# STM32_microcontroller_power.net
KiCad netlist of a schematic drawn in Altium Designer
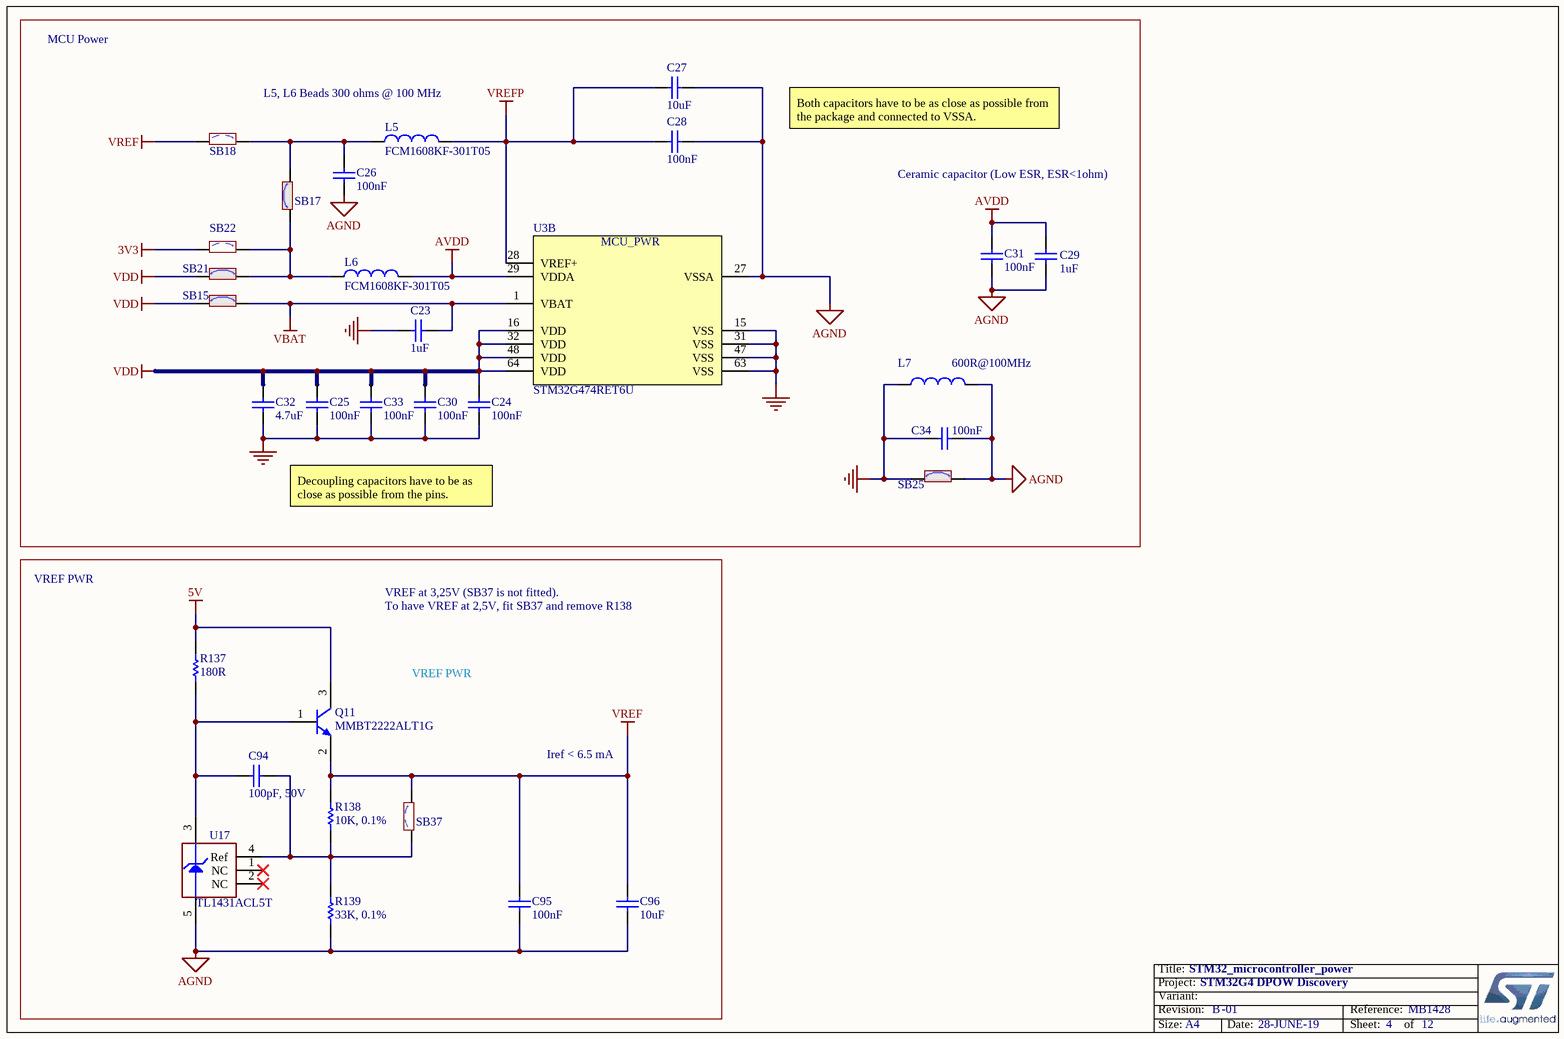
[diagram p0: STM32_microcontroller_power.SchDoc]

(export (version "E")
  (design (tool "Eeschema 10.0.6"))
  (components
    (comp (ref "C23")
      (value "1uF")
      (footprint "C0603")
      (description "Capacitor, MLCC, 1uF, 16V, X5R, 10%, 0603, T=0,8mm")
      (fields
        (field (name "INTERNAL_PART_NUMBER") "MCD-00010")
        (field (name "MANUFACTURER_PART_NUMBER") "CC0603KRX5R7BB105")
        (field (name "PROVIDED_BY") "SUBCO")
      )
      (libsource (lib "MCD_PARTS_database") (part "Capacitor"))
    )
    (comp (ref "C24")
      (value "100nF")
      (footprint "C0402")
      (description "Capacitor, MLCC, 100nF, 16V, X7R, 10%, 0402, T=0,5mm")
      (fields
        (field (name "INTERNAL_PART_NUMBER") "MCD-00102")
        (field (name "MANUFACTURER_PART_NUMBER") "CC0402KRX7R7BB104")
        (field (name "PROVIDED_BY") "SUBCO")
      )
      (libsource (lib "MCD_PARTS_database") (part "Capacitor"))
    )
    (comp (ref "C25")
      (value "100nF")
      (footprint "C0402")
      (description "Capacitor, MLCC, 100nF, 16V, X7R, 10%, 0402, T=0,5mm")
      (fields
        (field (name "INTERNAL_PART_NUMBER") "MCD-00102")
        (field (name "MANUFACTURER_PART_NUMBER") "CC0402KRX7R7BB104")
        (field (name "PROVIDED_BY") "SUBCO")
      )
      (libsource (lib "MCD_PARTS_database") (part "Capacitor"))
    )
    (comp (ref "C26")
      (value "100nF")
      (footprint "C0402")
      (description "Capacitor, MLCC, 100nF, 16V, X7R, 10%, 0402, T=0,5mm")
      (fields
        (field (name "INTERNAL_PART_NUMBER") "MCD-00102")
        (field (name "MANUFACTURER_PART_NUMBER") "CC0402KRX7R7BB104")
        (field (name "PROVIDED_BY") "SUBCO")
      )
      (libsource (lib "MCD_PARTS_database") (part "Capacitor"))
    )
    (comp (ref "C27")
      (value "10uF")
      (footprint "C0603")
      (description "Capacitor, MLCC, 10µF, 10V, X5R, 10%, 0603, T=0.8mm")
      (fields
        (field (name "INTERNAL_PART_NUMBER") "MCD-01124")
        (field (name "MANUFACTURER_PART_NUMBER") "GRM188R61A106KAAL")
        (field (name "PROVIDED_BY") "SUBCO")
      )
      (libsource (lib "MCD_PARTS_database") (part "Capacitor"))
    )
    (comp (ref "C28")
      (value "100nF")
      (footprint "C0402")
      (description "Capacitor, MLCC, 100nF, 16V, X7R, 10%, 0402, T=0,5mm")
      (fields
        (field (name "INTERNAL_PART_NUMBER") "MCD-00102")
        (field (name "MANUFACTURER_PART_NUMBER") "CC0402KRX7R7BB104")
        (field (name "PROVIDED_BY") "SUBCO")
      )
      (libsource (lib "MCD_PARTS_database") (part "Capacitor"))
    )
    (comp (ref "C29")
      (value "1uF")
      (footprint "C0603")
      (description "Capacitor, MLCC, 1uF, 16V, X5R, 10%, 0603, T=0,8mm")
      (fields
        (field (name "INTERNAL_PART_NUMBER") "MCD-00010")
        (field (name "MANUFACTURER_PART_NUMBER") "CC0603KRX5R7BB105")
        (field (name "PROVIDED_BY") "SUBCO")
      )
      (libsource (lib "MCD_PARTS_database") (part "Capacitor"))
    )
    (comp (ref "C30")
      (value "100nF")
      (footprint "C0402")
      (description "Capacitor, MLCC, 100nF, 16V, X7R, 10%, 0402, T=0,5mm")
      (fields
        (field (name "INTERNAL_PART_NUMBER") "MCD-00102")
        (field (name "MANUFACTURER_PART_NUMBER") "CC0402KRX7R7BB104")
        (field (name "PROVIDED_BY") "SUBCO")
      )
      (libsource (lib "MCD_PARTS_database") (part "Capacitor"))
    )
    (comp (ref "C31")
      (value "100nF")
      (footprint "C0402")
      (description "Capacitor, MLCC, 100nF, 16V, X7R, 10%, 0402, T=0,5mm")
      (fields
        (field (name "INTERNAL_PART_NUMBER") "MCD-00102")
        (field (name "MANUFACTURER_PART_NUMBER") "CC0402KRX7R7BB104")
        (field (name "PROVIDED_BY") "SUBCO")
      )
      (libsource (lib "MCD_PARTS_database") (part "Capacitor"))
    )
    (comp (ref "C32")
      (value "4.7uF")
      (footprint "C0603")
      (description "Capacitor, MLCC, 4.7uF, 16V, X5R, 10%, 0603, T=0.8mm")
      (fields
        (field (name "INTERNAL_PART_NUMBER") "MCD-00009")
        (field (name "MANUFACTURER_PART_NUMBER") "CC0603KRX5R7BB475")
        (field (name "PROVIDED_BY") "SUBCO")
      )
      (libsource (lib "MCD_PARTS_database") (part "Capacitor"))
    )
    (comp (ref "C33")
      (value "100nF")
      (footprint "C0402")
      (description "Capacitor, MLCC, 100nF, 16V, X7R, 10%, 0402, T=0,5mm")
      (fields
        (field (name "INTERNAL_PART_NUMBER") "MCD-00102")
        (field (name "MANUFACTURER_PART_NUMBER") "CC0402KRX7R7BB104")
        (field (name "PROVIDED_BY") "SUBCO")
      )
      (libsource (lib "MCD_PARTS_database") (part "Capacitor"))
    )
    (comp (ref "C34")
      (value "100nF")
      (footprint "C0402")
      (description "Capacitor, MLCC, 100nF, 16V, X7R, 10%, 0402, T=0,5mm")
      (fields
        (field (name "INTERNAL_PART_NUMBER") "MCD-00102")
        (field (name "MANUFACTURER_PART_NUMBER") "CC0402KRX7R7BB104")
        (field (name "PROVIDED_BY") "SUBCO")
      )
      (libsource (lib "MCD_PARTS_database") (part "Capacitor"))
    )
    (comp (ref "C94")
      (value "100pF, 50V")
      (footprint "C0603_H0P8")
      (description "Capacitor, MLCC, 100pF, 50V, NPO, 5%, 0603, T=0,8mm")
      (fields
        (field (name "INTERNAL_PART_NUMBER") "MCD-01648")
        (field (name "MANUFACTURER_PART_NUMBER") "CC0603JRNPO9BN101")
        (field (name "PROVIDED_BY") "SUBCO")
      )
      (libsource (lib "MCD_PARTS_database") (part "Capacitor"))
    )
    (comp (ref "C95")
      (value "100nF")
      (footprint "C0603")
      (description "Capacitor, MLCC, 100nF, 16V, X7R, 10%, 0603, T=0,8mm")
      (fields
        (field (name "INTERNAL_PART_NUMBER") "MCD-00211")
        (field (name "MANUFACTURER_PART_NUMBER") "CC0603KRX7R7BB104")
        (field (name "PROVIDED_BY") "SUBCO")
      )
      (libsource (lib "MCD_PARTS_database") (part "Capacitor"))
    )
    (comp (ref "C96")
      (value "10uF")
      (footprint "C0603")
      (description "Capacitor, MLCC, 10µF, 10V, X5R, 10%, 0603, T=0.8mm")
      (fields
        (field (name "INTERNAL_PART_NUMBER") "MCD-01124")
        (field (name "MANUFACTURER_PART_NUMBER") "GRM188R61A106KAAL")
        (field (name "PROVIDED_BY") "SUBCO")
      )
      (libsource (lib "MCD_PARTS_database") (part "Capacitor"))
    )
    (comp (ref "L5")
      (value "FCM1608KF-301T05")
      (footprint "L0603")
      (description "Bead,300R,500mA,0603")
      (fields
        (field (name "INTERNAL_PART_NUMBER") "MCD-01735")
        (field (name "MANUFACTURER") "TAI-TECH")
        (field (name "PROVIDED_BY") "SUBCO")
      )
      (libsource (lib "MCD_PARTS_database") (part "BEAD"))
    )
    (comp (ref "L6")
      (value "FCM1608KF-301T05")
      (footprint "L0603")
      (description "Bead,300R,500mA,0603")
      (fields
        (field (name "INTERNAL_PART_NUMBER") "MCD-01735")
        (field (name "MANUFACTURER") "TAI-TECH")
        (field (name "PROVIDED_BY") "SUBCO")
      )
      (libsource (lib "MCD_PARTS_database") (part "BEAD"))
    )
    (comp (ref "L7")
      (value "600R@100MHz")
      (footprint "L0603")
      (description "SMD Chip ferrite bead, 600R@100MHz +/-25%, 350mA, 500mohm DC, 0603, T=0.8mm")
      (fields
        (field (name "INTERNAL_PART_NUMBER") "MCD-00047")
        (field (name "MANUFACTURER_PART_NUMBER") "FCM1608KF-601T03")
        (field (name "PROVIDED_BY") "SUBCO")
      )
      (libsource (lib "MCD_PARTS_database") (part "BEAD"))
    )
    (comp (ref "Q11")
      (value "MMBT2222ALT1G")
      (footprint "NPN_SOT23")
      (description "NPN Bipolar Transistor")
      (fields
        (field (name "INTERNAL_PART_NUMBER") "MCD-01737")
        (field (name "MANUFACTURER") "ON SEMICONDUCTOR")
        (field (name "PROVIDED_BY") "SUBCO")
      )
      (libsource (lib "MCD_PARTS_database") (part "9013-SOT23"))
    )
    (comp (ref "R137")
      (value "180R")
      (footprint "R0603")
      (description "Resistor,180R,0603,1%,1/10W")
      (fields
        (field (name "INTERNAL_PART_NUMBER") "MCD-00342")
        (field (name "MANUFACTURER_PART_NUMBER") "RC0603FR-07180RL")
        (field (name "PROVIDED_BY") "SUBCO")
      )
      (libsource (lib "MCD_PARTS_database") (part "Resistor"))
    )
    (comp (ref "R138")
      (value "10K, 0.1%")
      (footprint "R0603")
      (description "Resistor, 10K, 0603, 0.1%,1/10W")
      (fields
        (field (name "INTERNAL_PART_NUMBER") "MCD-01669")
        (field (name "MANUFACTURER_PART_NUMBER") "ERA3AEB103V")
        (field (name "PROVIDED_BY") "SUBCO")
      )
      (libsource (lib "MCD_PARTS_database") (part "Resistor"))
    )
    (comp (ref "R139")
      (value "33K, 0.1%")
      (footprint "R0603")
      (description "Resistor, 33K, 0603, 0.1%,1/10W")
      (fields
        (field (name "INTERNAL_PART_NUMBER") "MCD-01670")
        (field (name "MANUFACTURER_PART_NUMBER") "ERA3AEB333V")
        (field (name "PROVIDED_BY") "SUBCO")
      )
      (libsource (lib "MCD_PARTS_database") (part "Resistor"))
    )
    (comp (ref "SB15")
      (value "~")
      (footprint "SOLDER-BRIDGE_R0603-0R")
      (description "Solder Bridge ON")
      (fields
        (field (name "INTERNAL_PART_NUMBER") "MCD-00071")
        (field (name "MANUFACTURER_PART_NUMBER") "RC0603JR-070RL")
        (field (name "PROVIDED_BY") "SUBCO")
      )
      (libsource (lib "") (part "SB_ON_1"))
    )
    (comp (ref "SB17")
      (value "~")
      (footprint "SOLDER-BRIDGE_R0603-0R")
      (description "Solder Bridge ON")
      (fields
        (field (name "INTERNAL_PART_NUMBER") "MCD-00071")
        (field (name "MANUFACTURER_PART_NUMBER") "RC0603JR-070RL")
        (field (name "PROVIDED_BY") "SUBCO")
      )
      (libsource (lib "MCD_PARTS_database") (part "SB_ON"))
    )
    (comp (ref "SB18")
      (value "~")
      (footprint "SOLDER-BRIDGE_R0603-0R")
      (description "Solder Bridge OFF")
      (fields
        (field (name "INTERNAL_PART_NUMBER") "MCD-00072")
        (field (name "MANUFACTURER_PART_NUMBER") "RC0603JR-070RL")
        (field (name "PROVIDED_BY") "SUBCO")
      )
      (libsource (lib "MCD_PARTS_database") (part "SB_OFF"))
    )
    (comp (ref "SB21")
      (value "~")
      (footprint "SOLDER-BRIDGE_R0603-0R")
      (description "Solder Bridge ON")
      (fields
        (field (name "INTERNAL_PART_NUMBER") "MCD-00071")
        (field (name "MANUFACTURER_PART_NUMBER") "RC0603JR-070RL")
        (field (name "PROVIDED_BY") "SUBCO")
      )
      (libsource (lib "") (part "SB_ON_1"))
    )
    (comp (ref "SB22")
      (value "~")
      (footprint "SOLDER-BRIDGE_R0603-0R")
      (description "Solder Bridge OFF")
      (fields
        (field (name "INTERNAL_PART_NUMBER") "MCD-00072")
        (field (name "MANUFACTURER_PART_NUMBER") "RC0603JR-070RL")
        (field (name "PROVIDED_BY") "SUBCO")
      )
      (libsource (lib "MCD_PARTS_database") (part "SB_OFF"))
    )
    (comp (ref "SB25")
      (value "~")
      (footprint "SOLDER-BRIDGE_R0603-0R")
      (description "Solder Bridge ON")
      (fields
        (field (name "INTERNAL_PART_NUMBER") "MCD-00071")
        (field (name "MANUFACTURER_PART_NUMBER") "RC0603JR-070RL")
        (field (name "PROVIDED_BY") "SUBCO")
      )
      (libsource (lib "") (part "SB_ON_1"))
    )
    (comp (ref "SB37")
      (value "~")
      (footprint "SOLDER-BRIDGE_R0603-0R")
      (description "Solder Bridge OFF")
      (fields
        (field (name "INTERNAL_PART_NUMBER") "MCD-00072")
        (field (name "MANUFACTURER_PART_NUMBER") "RC0603JR-070RL")
        (field (name "PROVIDED_BY") "SUBCO")
      )
      (libsource (lib "") (part "SB_OFF_1"))
    )
    (comp (ref "U3")
      (value "STM32G474RET6U")
      (footprint "ICC_LQFP64_10X10_P050")
      (description "STM32G474RET6U MCU, LQFP64 10x10, 1.6, 512KB Flash, 128KB SRAM")
      (fields
        (field (name "INTERNAL_PART_NUMBER") "MCD-01584")
        (field (name "MANUFACTURER") "STMICROELECTRONICS")
        (field (name "PROVIDED_BY") "SUBCO with ST control")
      )
      (libsource (lib "MCD_PARTS_database") (part "STM32G474RET6U"))
    )
    (comp (ref "U17")
      (value "TL1431ACL5T")
      (footprint "ICC_SOT23-5L_H1P45")
      (description "Programmable voltage reference")
      (fields
        (field (name "INTERNAL_PART_NUMBER") "MCD-01157")
        (field (name "MANUFACTURER") "STMICROELECTRONICS")
        (field (name "PROVIDED_BY") "SUBCO with ST control")
      )
      (libsource (lib "MCD_PARTS_database") (part "TL1431ACL5T"))
    )
  )
  (nets
    (net (code "1") (name "3V3") (class "Default")
      (node (ref "SB22") (pin "1") (pinfunction "1_1") (pintype "passive"))
    )
    (net (code "2") (name "5V") (class "Default")
      (node (ref "Q11") (pin "3") (pinfunction "C_3") (pintype "passive"))
      (node (ref "R137") (pin "2") (pinfunction "2_2") (pintype "passive"))
    )
    (net (code "3") (name "AGND") (class "Default")
      (node (ref "C26") (pin "1") (pinfunction "1_1") (pintype "passive"))
      (node (ref "C27") (pin "1") (pinfunction "1_1") (pintype "passive"))
      (node (ref "C28") (pin "2") (pinfunction "2_2") (pintype "passive"))
      (node (ref "C29") (pin "1") (pinfunction "1_1") (pintype "passive"))
      (node (ref "C31") (pin "1") (pinfunction "1_1") (pintype "passive"))
      (node (ref "C34") (pin "2") (pinfunction "2_2") (pintype "passive"))
      (node (ref "C95") (pin "1") (pinfunction "1_1") (pintype "passive"))
      (node (ref "C96") (pin "1") (pinfunction "1_1") (pintype "passive"))
      (node (ref "L7") (pin "2") (pinfunction "2_2") (pintype "passive"))
      (node (ref "R139") (pin "1") (pinfunction "1_1") (pintype "passive"))
      (node (ref "SB25") (pin "2") (pinfunction "2_2") (pintype "passive"))
      (node (ref "U17") (pin "5") (pinfunction "Anode_5") (pintype "passive"))
      (node (ref "U3") (pin "27") (pinfunction "VSSA_27") (pintype "passive"))
    )
    (net (code "4") (name "AVDD") (class "Default")
      (node (ref "C29") (pin "2") (pinfunction "2_2") (pintype "passive"))
      (node (ref "C31") (pin "2") (pinfunction "2_2") (pintype "passive"))
      (node (ref "L6") (pin "2") (pinfunction "2_2") (pintype "passive"))
      (node (ref "U3") (pin "29") (pinfunction "VDDA_29") (pintype "passive"))
    )
    (net (code "5") (name "GND") (class "Default")
      (node (ref "C23") (pin "1") (pinfunction "1_1") (pintype "passive"))
      (node (ref "C24") (pin "1") (pinfunction "1_1") (pintype "passive"))
      (node (ref "C25") (pin "1") (pinfunction "1_1") (pintype "passive"))
      (node (ref "C30") (pin "1") (pinfunction "1_1") (pintype "passive"))
      (node (ref "C32") (pin "1") (pinfunction "1_1") (pintype "passive"))
      (node (ref "C33") (pin "1") (pinfunction "1_1") (pintype "passive"))
      (node (ref "C34") (pin "1") (pinfunction "1_1") (pintype "passive"))
      (node (ref "L7") (pin "1") (pinfunction "1_1") (pintype "passive"))
      (node (ref "SB25") (pin "1") (pinfunction "1_1") (pintype "passive"))
      (node (ref "U3") (pin "15") (pinfunction "VSS_15") (pintype "passive"))
      (node (ref "U3") (pin "31") (pinfunction "VSS_31") (pintype "passive"))
      (node (ref "U3") (pin "47") (pinfunction "VSS_47") (pintype "passive"))
      (node (ref "U3") (pin "63") (pinfunction "VSS_63") (pintype "passive"))
    )
    (net (code "6") (name "Net-(C26-Pad2)") (class "Default")
      (node (ref "C26") (pin "2") (pinfunction "2_2") (pintype "passive"))
      (node (ref "L5") (pin "1") (pinfunction "1_1") (pintype "passive"))
      (node (ref "SB17") (pin "2") (pinfunction "2_2") (pintype "passive"))
      (node (ref "SB18") (pin "2") (pinfunction "2_2") (pintype "passive"))
    )
    (net (code "7") (name "Net-(L6-Pad1)") (class "Default")
      (node (ref "L6") (pin "1") (pinfunction "1_1") (pintype "passive"))
      (node (ref "SB17") (pin "1") (pinfunction "1_1") (pintype "passive"))
      (node (ref "SB21") (pin "2") (pinfunction "2_2") (pintype "passive"))
      (node (ref "SB22") (pin "2") (pinfunction "2_2") (pintype "passive"))
    )
    (net (code "8") (name "Net-(Q11-B)") (class "Default")
      (node (ref "C94") (pin "1") (pinfunction "1_1") (pintype "passive"))
      (node (ref "Q11") (pin "1") (pinfunction "B_1") (pintype "passive"))
      (node (ref "R137") (pin "1") (pinfunction "1_1") (pintype "passive"))
      (node (ref "U17") (pin "3") (pinfunction "Cathode_3") (pintype "passive"))
    )
    (net (code "9") (name "Net-(U17-Ref)") (class "Default")
      (node (ref "C94") (pin "2") (pinfunction "2_2") (pintype "passive"))
      (node (ref "R138") (pin "1") (pinfunction "1_1") (pintype "passive"))
      (node (ref "R139") (pin "2") (pinfunction "2_2") (pintype "passive"))
      (node (ref "SB37") (pin "1") (pinfunction "1_1") (pintype "passive"))
      (node (ref "U17") (pin "4") (pinfunction "Ref_4") (pintype "passive"))
    )
    (net (code "10") (name "VBAT") (class "Default")
      (node (ref "C23") (pin "2") (pinfunction "2_2") (pintype "passive"))
      (node (ref "SB15") (pin "2") (pinfunction "2_2") (pintype "passive"))
      (node (ref "U3") (pin "1") (pinfunction "VBAT_1") (pintype "passive"))
    )
    (net (code "11") (name "VDD") (class "Default")
      (node (ref "C24") (pin "2") (pinfunction "2_2") (pintype "passive"))
      (node (ref "C25") (pin "2") (pinfunction "2_2") (pintype "passive"))
      (node (ref "C30") (pin "2") (pinfunction "2_2") (pintype "passive"))
      (node (ref "C32") (pin "2") (pinfunction "2_2") (pintype "passive"))
      (node (ref "C33") (pin "2") (pinfunction "2_2") (pintype "passive"))
      (node (ref "SB15") (pin "1") (pinfunction "1_1") (pintype "passive"))
      (node (ref "SB21") (pin "1") (pinfunction "1_1") (pintype "passive"))
      (node (ref "U3") (pin "16") (pinfunction "VDD_16") (pintype "passive"))
      (node (ref "U3") (pin "32") (pinfunction "VDD_32") (pintype "passive"))
      (node (ref "U3") (pin "48") (pinfunction "VDD_48") (pintype "passive"))
      (node (ref "U3") (pin "64") (pinfunction "VDD_64") (pintype "passive"))
    )
    (net (code "12") (name "VREF") (class "Default")
      (node (ref "C95") (pin "2") (pinfunction "2_2") (pintype "passive"))
      (node (ref "C96") (pin "2") (pinfunction "2_2") (pintype "passive"))
      (node (ref "Q11") (pin "2") (pinfunction "E_2") (pintype "passive"))
      (node (ref "R138") (pin "2") (pinfunction "2_2") (pintype "passive"))
      (node (ref "SB18") (pin "1") (pinfunction "1_1") (pintype "passive"))
      (node (ref "SB37") (pin "2") (pinfunction "2_2") (pintype "passive"))
    )
    (net (code "13") (name "VREFP") (class "Default")
      (node (ref "C27") (pin "2") (pinfunction "2_2") (pintype "passive"))
      (node (ref "C28") (pin "1") (pinfunction "1_1") (pintype "passive"))
      (node (ref "L5") (pin "2") (pinfunction "2_2") (pintype "passive"))
      (node (ref "U3") (pin "28") (pinfunction "VREF+_28") (pintype "passive"))
    )
    (net (code "14") (name "unconnected-(U17-NC-Pad1)") (class "Default")
      (node (ref "U17") (pin "1") (pinfunction "NC_1") (pintype "passive+no_connect"))
    )
    (net (code "15") (name "unconnected-(U17-NC-Pad2)") (class "Default")
      (node (ref "U17") (pin "2") (pinfunction "NC_2") (pintype "passive+no_connect"))
    )
  )
)
